# ReboostV2_Power.net
KiCad netlist of a schematic drawn in Altium Designer
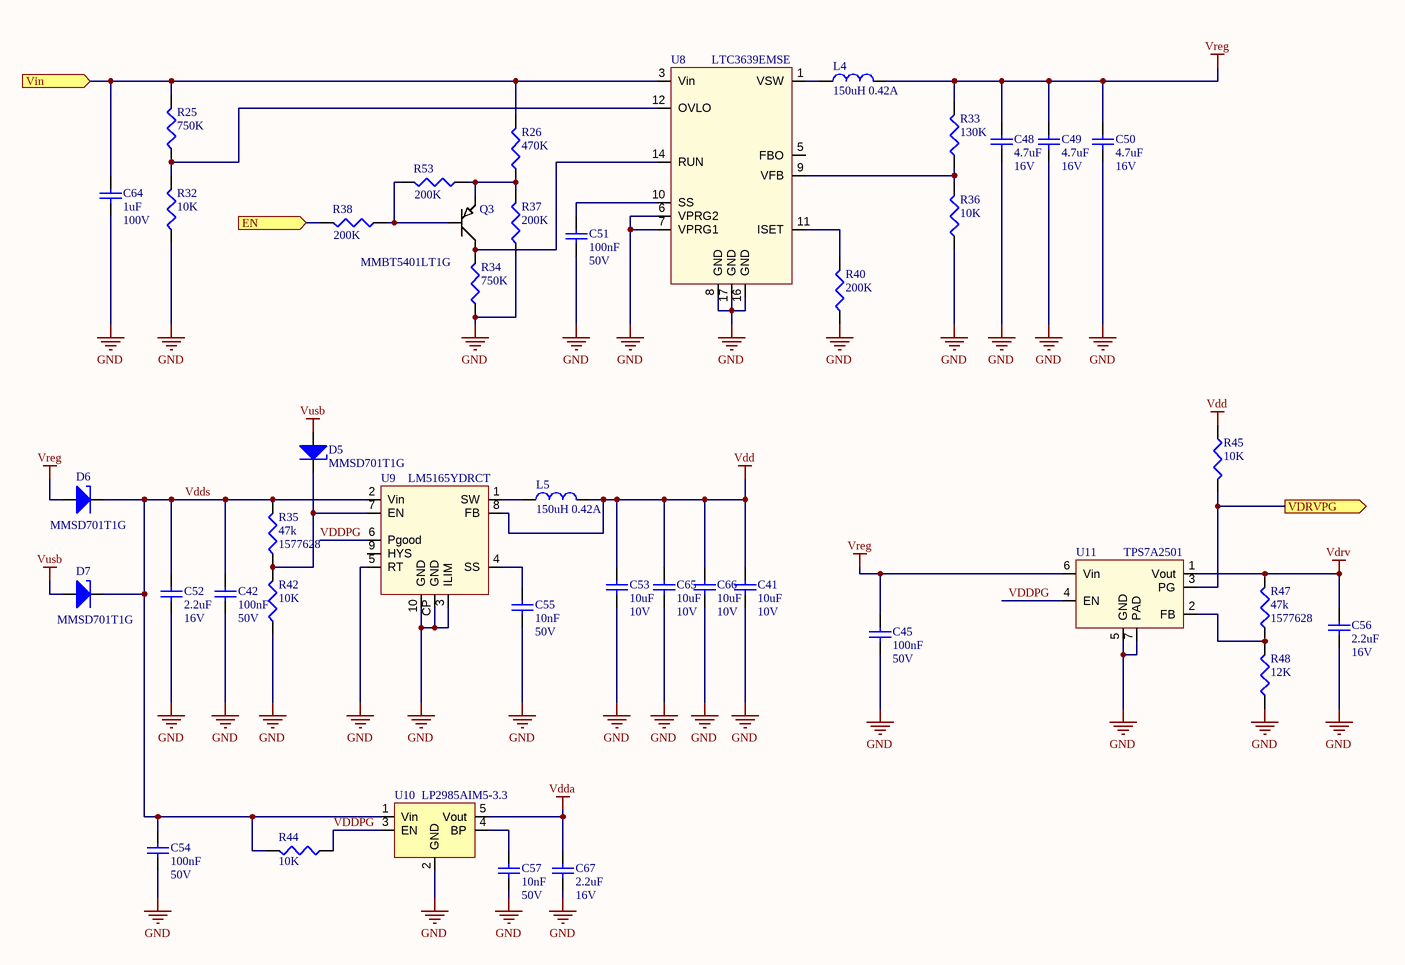
[diagram p0: ReboostV2_Power.SchDoc]

(export (version "E")
  (design (tool "Eeschema 10.0.6"))
  (components
    (comp (ref "C41")
      (value "10uF")
      (footprint "C-0805")
      (description "Capacitor, 10uF, 10V, X7R")
      (fields (field (name "VOLTAGE RATING") "10V"))
      (libsource (lib "AR_Capacitors_Ceramic") (part "10uF/0805/CER/10V"))
    )
    (comp (ref "C42")
      (value "100nF")
      (footprint "C0603")
      (description "Capacitor, 100nF, 50V, X7R")
      (fields (field (name "VOLTAGE RATING") "50V"))
      (libsource (lib "AR_Capacitors_Ceramic") (part "100nF/0603/CER/50V"))
    )
    (comp (ref "C45")
      (value "100nF")
      (footprint "C0603")
      (description "Capacitor, 100nF, 50V, X7R")
      (fields (field (name "VOLTAGE RATING") "50V"))
      (libsource (lib "AR_Capacitors_Ceramic") (part "100nF/0603/CER/50V"))
    )
    (comp (ref "C48")
      (value "4.7uF")
      (footprint "C-0805")
      (description "Capacitor, 4.7uF, 16V, X7R")
      (fields (field (name "VOLTAGE RATING") "16V"))
      (libsource (lib "AR_Capacitors_Ceramic") (part "4.7uF/0805/CER/16V"))
    )
    (comp (ref "C49")
      (value "4.7uF")
      (footprint "C-0805")
      (description "Capacitor, 4.7uF, 16V, X7R")
      (fields (field (name "VOLTAGE RATING") "16V"))
      (libsource (lib "AR_Capacitors_Ceramic") (part "4.7uF/0805/CER/16V"))
    )
    (comp (ref "C50")
      (value "4.7uF")
      (footprint "C-0805")
      (description "Capacitor, 4.7uF, 16V, X7R")
      (fields (field (name "VOLTAGE RATING") "16V"))
      (libsource (lib "AR_Capacitors_Ceramic") (part "4.7uF/0805/CER/16V"))
    )
    (comp (ref "C51")
      (value "100nF")
      (footprint "C0603")
      (description "Capacitor, 100nF, 50V, X7R")
      (fields (field (name "VOLTAGE RATING") "50V"))
      (libsource (lib "AR_Capacitors_Ceramic") (part "100nF/0603/CER/50V"))
    )
    (comp (ref "C52")
      (value "2.2uF")
      (footprint "C0603")
      (description "Capacitor, 2.2uF, 16V, X5R")
      (fields (field (name "VOLTAGE RATING") "16V"))
      (libsource (lib "AR_Capacitors_Ceramic") (part "2.2uF/0603/CER/16V"))
    )
    (comp (ref "C53")
      (value "10uF")
      (footprint "C-0805")
      (description "Capacitor, 10uF, 10V, X7R")
      (fields (field (name "VOLTAGE RATING") "10V"))
      (libsource (lib "AR_Capacitors_Ceramic") (part "10uF/0805/CER/10V"))
    )
    (comp (ref "C54")
      (value "100nF")
      (footprint "C0603")
      (description "Capacitor, 100nF, 50V, X7R")
      (fields (field (name "VOLTAGE RATING") "50V"))
      (libsource (lib "AR_Capacitors_Ceramic") (part "100nF/0603/CER/50V"))
    )
    (comp (ref "C55")
      (value "10nF")
      (footprint "C0603")
      (description "Capacitor, 10nF, 50V, X7R")
      (fields (field (name "VOLTAGE RATING") "50V"))
      (libsource (lib "AR_Capacitors_Ceramic") (part "10nF/0603/CER/50V"))
    )
    (comp (ref "C56")
      (value "2.2uF")
      (footprint "C0603")
      (description "Capacitor, 2.2uF, 16V, X5R")
      (fields (field (name "VOLTAGE RATING") "16V"))
      (libsource (lib "AR_Capacitors_Ceramic") (part "2.2uF/0603/CER/16V"))
    )
    (comp (ref "C57")
      (value "10nF")
      (footprint "C0603")
      (description "Capacitor, 10nF, 50V, X7R")
      (fields (field (name "VOLTAGE RATING") "50V"))
      (libsource (lib "AR_Capacitors_Ceramic") (part "10nF/0603/CER/50V"))
    )
    (comp (ref "C64")
      (value "1uF")
      (footprint "C-1206")
      (description "Capacitor, 1uF, 100V, X7R")
      (fields (field (name "VOLTAGE RATING") "100V"))
      (libsource (lib "AR_Capacitors_Ceramic") (part "1uF/1206/CER/100V"))
    )
    (comp (ref "C65")
      (value "10uF")
      (footprint "C-0805")
      (description "Capacitor, 10uF, 10V, X7R")
      (fields (field (name "VOLTAGE RATING") "10V"))
      (libsource (lib "AR_Capacitors_Ceramic") (part "10uF/0805/CER/10V"))
    )
    (comp (ref "C66")
      (value "10uF")
      (footprint "C-0805")
      (description "Capacitor, 10uF, 10V, X7R")
      (fields (field (name "VOLTAGE RATING") "10V"))
      (libsource (lib "AR_Capacitors_Ceramic") (part "10uF/0805/CER/10V"))
    )
    (comp (ref "C67")
      (value "2.2uF")
      (footprint "C0603")
      (description "Capacitor, 2.2uF, 16V, X5R")
      (fields (field (name "VOLTAGE RATING") "16V"))
      (libsource (lib "AR_Capacitors_Ceramic") (part "2.2uF/0603/CER/16V"))
    )
    (comp (ref "D5")
      (value "MMSD701T1G")
      (footprint "SOD123 - B")
      (description "Diode Schottky, Vrrm: 70V, If: 0.2A, Vf: 0.5V")
      (libsource (lib "AR_Diodes") (part "MMSD701T1G"))
    )
    (comp (ref "D6")
      (value "MMSD701T1G")
      (footprint "SOD123 - B")
      (description "Diode Schottky, Vrrm: 70V, If: 0.2A, Vf: 0.5V")
      (libsource (lib "AR_Diodes") (part "MMSD701T1G"))
    )
    (comp (ref "D7")
      (value "MMSD701T1G")
      (footprint "SOD123 - B")
      (description "Diode Schottky, Vrrm: 70V, If: 0.2A, Vf: 0.5V")
      (libsource (lib "AR_Diodes") (part "MMSD701T1G"))
    )
    (comp (ref "L4")
      (value "150uH 0.42A")
      (footprint "WE-TPC 4828, MH")
      (description "150UH, 30%, 0.42A")
      (libsource (lib "AR_Inductors") (part "744043151"))
    )
    (comp (ref "L5")
      (value "150uH 0.42A")
      (footprint "WE-TPC 4828, MH")
      (description "150UH, 30%, 0.42A")
      (libsource (lib "AR_Inductors") (part "744043151"))
    )
    (comp (ref "Q3")
      (value "MMBT5401LT1G")
      (footprint "SOT-23")
      (description "Transistor, PNP, Vce:-150V, Vcb:-160V, Veb:-5V, Ic:-0,5A, Hfe:60 to 240")
      (libsource (lib "AR_Transistors") (part "MMBT5401LT1G"))
    )
    (comp (ref "R25")
      (value "750K")
      (footprint "0603")
      (description "Resistor, 750K, 1%, 0.063W, 50V, 100PPM, 0603")
      (libsource (lib "AR_Resistors_SMD") (part "750K/0603/0063W/50V"))
    )
    (comp (ref "R26")
      (value "470K")
      (footprint "0603")
      (description "Resistor, 470K, 1%, 0.063W, 50V, 100PPM, 0603")
      (libsource (lib "AR_Resistors_SMD") (part "470K/0603/0063W/50V"))
    )
    (comp (ref "R32")
      (value "10K")
      (footprint "0603")
      (description "Resistor, 10K, 1%, 0.063W, 50V, 100PPM, 0603")
      (libsource (lib "AR_Resistors_SMD") (part "10K/0603/0063W/50V"))
    )
    (comp (ref "R33")
      (value "130K")
      (footprint "0603")
      (description "Resistor, 130K, 1%, 0.063W, 50V, 100PPM, 0603")
      (libsource (lib "AR_Resistors_SMD") (part "130K/0603/0063W/50V"))
    )
    (comp (ref "R34")
      (value "750K")
      (footprint "0603")
      (description "Resistor, 750K, 1%, 0.063W, 50V, 100PPM, 0603")
      (libsource (lib "AR_Resistors_SMD") (part "750K/0603/0063W/50V"))
    )
    (comp (ref "R35")
      (value "47k")
      (footprint "0603")
      (description "Resistor, 47K, 0.1%, 0.063W, 50V, 100PPM, 0603")
      (fields (field (name "SUPPLIER PART NUMBER 1") "1577628"))
      (libsource (lib "AR_Resistors_SMD") (part "47K/0603/0063W/50V_1"))
    )
    (comp (ref "R36")
      (value "10K")
      (footprint "0603")
      (description "Resistor, 10K, 1%, 0.063W, 50V, 100PPM, 0603")
      (libsource (lib "AR_Resistors_SMD") (part "10K/0603/0063W/50V"))
    )
    (comp (ref "R37")
      (value "200K")
      (footprint "0603")
      (description "Resistor, 200K, 1%, 0.063W, 50V, 100PPM, 0603")
      (libsource (lib "AR_Resistors_SMD") (part "200K/0603/0063W/50V"))
    )
    (comp (ref "R38")
      (value "200K")
      (footprint "0603")
      (description "Resistor, 200K, 1%, 0.063W, 50V, 100PPM, 0603")
      (libsource (lib "AR_Resistors_SMD") (part "200K/0603/0063W/50V"))
    )
    (comp (ref "R40")
      (value "200K")
      (footprint "0603")
      (description "Resistor, 200K, 1%, 0.1W, 75V, 100PPM, 0603")
      (libsource (lib "AR_Resistors_SMD") (part "200K/0603/0100W/75V"))
    )
    (comp (ref "R42")
      (value "10K")
      (footprint "0603")
      (description "Resistor, 10K, 1%, 0.063W, 50V, 100PPM, 0603")
      (libsource (lib "AR_Resistors_SMD") (part "10K/0603/0063W/50V"))
    )
    (comp (ref "R44")
      (value "10K")
      (footprint "0603")
      (description "Resistor, 10K, 1%, 0.063W, 50V, 100PPM, 0603")
      (libsource (lib "AR_Resistors_SMD") (part "10K/0603/0063W/50V"))
    )
    (comp (ref "R45")
      (value "10K")
      (footprint "0603")
      (description "Resistor, 10K, 1%, 0.063W, 50V, 100PPM, 0603")
      (libsource (lib "AR_Resistors_SMD") (part "10K/0603/0063W/50V"))
    )
    (comp (ref "R47")
      (value "47k")
      (footprint "0603")
      (description "Resistor, 47K, 0.1%, 0.063W, 50V, 100PPM, 0603")
      (fields (field (name "SUPPLIER PART NUMBER 1") "1577628"))
      (libsource (lib "AR_Resistors_SMD") (part "47K/0603/0063W/50V_1"))
    )
    (comp (ref "R48")
      (value "12K")
      (footprint "0603")
      (description "Resistor, 12K, 1%, 0.063W, 50V, 100PPM, 0603")
      (libsource (lib "AR_Resistors_SMD") (part "12K/0603/0063W/50V"))
    )
    (comp (ref "R53")
      (value "200K")
      (footprint "0603")
      (description "Resistor, 200K, 1%, 0.063W, 50V, 100PPM, 0603")
      (libsource (lib "AR_Resistors_SMD") (part "200K/0603/0063W/50V"))
    )
    (comp (ref "U8")
      (value "LTC3639EMSE")
      (footprint "MSE1612")
      (description "High Efficiency, 150V 100mA Synchronous Step-Down Regulator")
      (libsource (lib "AR_Vreg") (part "LTC3639EMSE"))
    )
    (comp (ref "U9")
      (value "LM5165YDRCT")
      (footprint "PWSON10")
      (description "Buck Vreg 150mA 3V3 out 5-65Vin")
      (libsource (lib "AR_Vreg") (part "LM5165Y"))
    )
    (comp (ref "U10")
      (value "LP2985AIM5-3.3")
      (footprint "SOT-23-5")
      (description "LDO, 0.3VDO, 3.3V, 0.15A, 1%")
      (libsource (lib "AR_Vreg") (part "LP2985AIM5-3.3"))
    )
    (comp (ref "U11")
      (value "TPS7A2501")
      (footprint "WSON-6")
      (description "TPS7A25 300-mA,18-V, Ultra-LowIQ, Low-DropoutLinearVoltageRegulatorWith Power-Good")
      (libsource (lib "AR_Vreg") (part "TPS7A2501DRVT"))
    )
  )
  (nets
    (net (code "1") (name "/EN") (class "Default")
      (node (ref "R38") (pin "2") (pinfunction "2_2") (pintype "passive"))
    )
    (net (code "2") (name "/VDDPG") (class "Default")
      (node (ref "R44") (pin "1") (pinfunction "1_1") (pintype "passive"))
      (node (ref "U10") (pin "3") (pinfunction "EN_3") (pintype "passive"))
      (node (ref "U11") (pin "4") (pinfunction "EN_4") (pintype "passive"))
      (node (ref "U9") (pin "6") (pinfunction "Pgood_6") (pintype "passive"))
    )
    (net (code "3") (name "/VDRVPG") (class "Default")
      (node (ref "R45") (pin "2") (pinfunction "2_2") (pintype "passive"))
      (node (ref "U11") (pin "3") (pinfunction "PG_3") (pintype "passive"))
    )
    (net (code "4") (name "/Vdds") (class "Default")
      (node (ref "C42") (pin "2") (pinfunction "2_2") (pintype "passive"))
      (node (ref "C52") (pin "2") (pinfunction "2_2") (pintype "passive"))
      (node (ref "C54") (pin "2") (pinfunction "2_2") (pintype "passive"))
      (node (ref "D6") (pin "2") (pinfunction "K_2") (pintype "passive"))
      (node (ref "D7") (pin "2") (pinfunction "K_2") (pintype "passive"))
      (node (ref "R35") (pin "2") (pinfunction "2_2") (pintype "passive"))
      (node (ref "R44") (pin "2") (pinfunction "2_2") (pintype "passive"))
      (node (ref "U10") (pin "1") (pinfunction "Vin_1") (pintype "passive"))
      (node (ref "U9") (pin "2") (pinfunction "Vin_2") (pintype "passive"))
    )
    (net (code "5") (name "/Vin") (class "Default")
      (node (ref "C64") (pin "2") (pinfunction "2_2") (pintype "passive"))
      (node (ref "R25") (pin "2") (pinfunction "2_2") (pintype "passive"))
      (node (ref "R26") (pin "2") (pinfunction "2_2") (pintype "passive"))
      (node (ref "U8") (pin "3") (pinfunction "Vin_3") (pintype "passive"))
    )
    (net (code "6") (name "GND") (class "Default")
      (node (ref "C41") (pin "1") (pinfunction "1_1") (pintype "passive"))
      (node (ref "C42") (pin "1") (pinfunction "1_1") (pintype "passive"))
      (node (ref "C45") (pin "1") (pinfunction "1_1") (pintype "passive"))
      (node (ref "C48") (pin "1") (pinfunction "1_1") (pintype "passive"))
      (node (ref "C49") (pin "1") (pinfunction "1_1") (pintype "passive"))
      (node (ref "C50") (pin "1") (pinfunction "1_1") (pintype "passive"))
      (node (ref "C51") (pin "1") (pinfunction "1_1") (pintype "passive"))
      (node (ref "C52") (pin "1") (pinfunction "1_1") (pintype "passive"))
      (node (ref "C53") (pin "1") (pinfunction "1_1") (pintype "passive"))
      (node (ref "C54") (pin "1") (pinfunction "1_1") (pintype "passive"))
      (node (ref "C55") (pin "1") (pinfunction "1_1") (pintype "passive"))
      (node (ref "C56") (pin "1") (pinfunction "1_1") (pintype "passive"))
      (node (ref "C57") (pin "1") (pinfunction "1_1") (pintype "passive"))
      (node (ref "C64") (pin "1") (pinfunction "1_1") (pintype "passive"))
      (node (ref "C65") (pin "1") (pinfunction "1_1") (pintype "passive"))
      (node (ref "C66") (pin "1") (pinfunction "1_1") (pintype "passive"))
      (node (ref "C67") (pin "1") (pinfunction "1_1") (pintype "passive"))
      (node (ref "R32") (pin "1") (pinfunction "1_1") (pintype "passive"))
      (node (ref "R34") (pin "1") (pinfunction "1_1") (pintype "passive"))
      (node (ref "R36") (pin "1") (pinfunction "1_1") (pintype "passive"))
      (node (ref "R37") (pin "1") (pinfunction "1_1") (pintype "passive"))
      (node (ref "R40") (pin "1") (pinfunction "1_1") (pintype "passive"))
      (node (ref "R42") (pin "1") (pinfunction "1_1") (pintype "passive"))
      (node (ref "R48") (pin "1") (pinfunction "1_1") (pintype "passive"))
      (node (ref "U10") (pin "2") (pinfunction "GND_2") (pintype "passive"))
      (node (ref "U11") (pin "5") (pinfunction "GND_5") (pintype "passive"))
      (node (ref "U11") (pin "7") (pinfunction "PAD_7") (pintype "passive"))
      (node (ref "U8") (pin "16") (pinfunction "GND_16") (pintype "passive"))
      (node (ref "U8") (pin "17") (pinfunction "GND_17") (pintype "passive"))
      (node (ref "U8") (pin "6") (pinfunction "VPRG2_6") (pintype "passive"))
      (node (ref "U8") (pin "7") (pinfunction "VPRG1_7") (pintype "passive"))
      (node (ref "U8") (pin "8") (pinfunction "GND_8") (pintype "passive"))
      (node (ref "U9") (pin "10") (pinfunction "GND_10") (pintype "passive"))
      (node (ref "U9") (pin "3") (pinfunction "ILIM_3") (pintype "passive"))
      (node (ref "U9") (pin "5") (pinfunction "RT_5") (pintype "passive"))
      (node (ref "U9") (pin "CP") (pinfunction "GND_CP") (pintype "passive"))
    )
    (net (code "7") (name "Net-(D5-K)") (class "Default")
      (node (ref "D5") (pin "2") (pinfunction "K_2") (pintype "passive"))
      (node (ref "R35") (pin "1") (pinfunction "1_1") (pintype "passive"))
      (node (ref "R42") (pin "2") (pinfunction "2_2") (pintype "passive"))
      (node (ref "U9") (pin "7") (pinfunction "EN_7") (pintype "passive"))
    )
    (net (code "8") (name "Net-(Q3-Pad1)") (class "Default")
      (node (ref "Q3") (pin "1") (pinfunction "1_1") (pintype "passive"))
      (node (ref "R38") (pin "1") (pinfunction "1_1") (pintype "passive"))
      (node (ref "R53") (pin "2") (pinfunction "2_2") (pintype "passive"))
    )
    (net (code "9") (name "Net-(Q3-Pad2)") (class "Default")
      (node (ref "Q3") (pin "2") (pinfunction "2_2") (pintype "passive"))
      (node (ref "R26") (pin "1") (pinfunction "1_1") (pintype "passive"))
      (node (ref "R37") (pin "2") (pinfunction "2_2") (pintype "passive"))
      (node (ref "R53") (pin "1") (pinfunction "1_1") (pintype "passive"))
    )
    (net (code "10") (name "Net-(U8-ISET)") (class "Default")
      (node (ref "R40") (pin "2") (pinfunction "2_2") (pintype "passive"))
      (node (ref "U8") (pin "11") (pinfunction "ISET_11") (pintype "passive"))
    )
    (net (code "11") (name "Net-(U8-OVLO)") (class "Default")
      (node (ref "R25") (pin "1") (pinfunction "1_1") (pintype "passive"))
      (node (ref "R32") (pin "2") (pinfunction "2_2") (pintype "passive"))
      (node (ref "U8") (pin "12") (pinfunction "OVLO_12") (pintype "passive"))
    )
    (net (code "12") (name "Net-(U8-RUN)") (class "Default")
      (node (ref "Q3") (pin "3") (pinfunction "3_3") (pintype "passive"))
      (node (ref "R34") (pin "2") (pinfunction "2_2") (pintype "passive"))
      (node (ref "U8") (pin "14") (pinfunction "RUN_14") (pintype "passive"))
    )
    (net (code "13") (name "Net-(U8-SS)") (class "Default")
      (node (ref "C51") (pin "2") (pinfunction "2_2") (pintype "passive"))
      (node (ref "U8") (pin "10") (pinfunction "SS_10") (pintype "passive"))
    )
    (net (code "14") (name "Net-(U8-VFB)") (class "Default")
      (node (ref "R33") (pin "1") (pinfunction "1_1") (pintype "passive"))
      (node (ref "R36") (pin "2") (pinfunction "2_2") (pintype "passive"))
      (node (ref "U8") (pin "9") (pinfunction "VFB_9") (pintype "passive"))
    )
    (net (code "15") (name "Net-(U8-VSW)") (class "Default")
      (node (ref "L4") (pin "1") (pinfunction "1_1") (pintype "passive"))
      (node (ref "U8") (pin "1") (pinfunction "VSW_1") (pintype "passive"))
    )
    (net (code "16") (name "Net-(U9-SS)") (class "Default")
      (node (ref "C55") (pin "2") (pinfunction "2_2") (pintype "passive"))
      (node (ref "U9") (pin "4") (pinfunction "SS_4") (pintype "passive"))
    )
    (net (code "17") (name "Net-(U9-SW)") (class "Default")
      (node (ref "L5") (pin "1") (pinfunction "1_1") (pintype "passive"))
      (node (ref "U9") (pin "1") (pinfunction "SW_1") (pintype "passive"))
    )
    (net (code "18") (name "Net-(U10-BP)") (class "Default")
      (node (ref "C57") (pin "2") (pinfunction "2_2") (pintype "passive"))
      (node (ref "U10") (pin "4") (pinfunction "BP_4") (pintype "passive"))
    )
    (net (code "19") (name "Net-(U11-FB)") (class "Default")
      (node (ref "R47") (pin "1") (pinfunction "1_1") (pintype "passive"))
      (node (ref "R48") (pin "2") (pinfunction "2_2") (pintype "passive"))
      (node (ref "U11") (pin "2") (pinfunction "FB_2") (pintype "passive"))
    )
    (net (code "20") (name "Vdd") (class "Default")
      (node (ref "C41") (pin "2") (pinfunction "2_2") (pintype "passive"))
      (node (ref "C53") (pin "2") (pinfunction "2_2") (pintype "passive"))
      (node (ref "C65") (pin "2") (pinfunction "2_2") (pintype "passive"))
      (node (ref "C66") (pin "2") (pinfunction "2_2") (pintype "passive"))
      (node (ref "L5") (pin "2") (pinfunction "2_2") (pintype "passive"))
      (node (ref "R45") (pin "1") (pinfunction "1_1") (pintype "passive"))
      (node (ref "U9") (pin "8") (pinfunction "FB_8") (pintype "passive"))
    )
    (net (code "21") (name "Vdda") (class "Default")
      (node (ref "C67") (pin "2") (pinfunction "2_2") (pintype "passive"))
      (node (ref "U10") (pin "5") (pinfunction "Vout_5") (pintype "passive"))
    )
    (net (code "22") (name "Vdrv") (class "Default")
      (node (ref "C56") (pin "2") (pinfunction "2_2") (pintype "passive"))
      (node (ref "R47") (pin "2") (pinfunction "2_2") (pintype "passive"))
      (node (ref "U11") (pin "1") (pinfunction "Vout_1") (pintype "passive"))
    )
    (net (code "23") (name "Vreg") (class "Default")
      (node (ref "C45") (pin "2") (pinfunction "2_2") (pintype "passive"))
      (node (ref "C48") (pin "2") (pinfunction "2_2") (pintype "passive"))
      (node (ref "C49") (pin "2") (pinfunction "2_2") (pintype "passive"))
      (node (ref "C50") (pin "2") (pinfunction "2_2") (pintype "passive"))
      (node (ref "D6") (pin "1") (pinfunction "A_1") (pintype "passive"))
      (node (ref "L4") (pin "2") (pinfunction "2_2") (pintype "passive"))
      (node (ref "R33") (pin "2") (pinfunction "2_2") (pintype "passive"))
      (node (ref "U11") (pin "6") (pinfunction "Vin_6") (pintype "passive"))
    )
    (net (code "24") (name "Vusb") (class "Default")
      (node (ref "D5") (pin "1") (pinfunction "A_1") (pintype "passive"))
      (node (ref "D7") (pin "1") (pinfunction "A_1") (pintype "passive"))
    )
    (net (code "25") (name "unconnected-(U8-FBO-Pad5)") (class "Default")
      (node (ref "U8") (pin "5") (pinfunction "FBO_5") (pintype "passive"))
    )
    (net (code "26") (name "unconnected-(U9-HYS-Pad9)") (class "Default")
      (node (ref "U9") (pin "9") (pinfunction "HYS_9") (pintype "passive"))
    )
  )
)
